# raspi-rnc.net
KiCad netlist of a schematic drawn in EAGLE
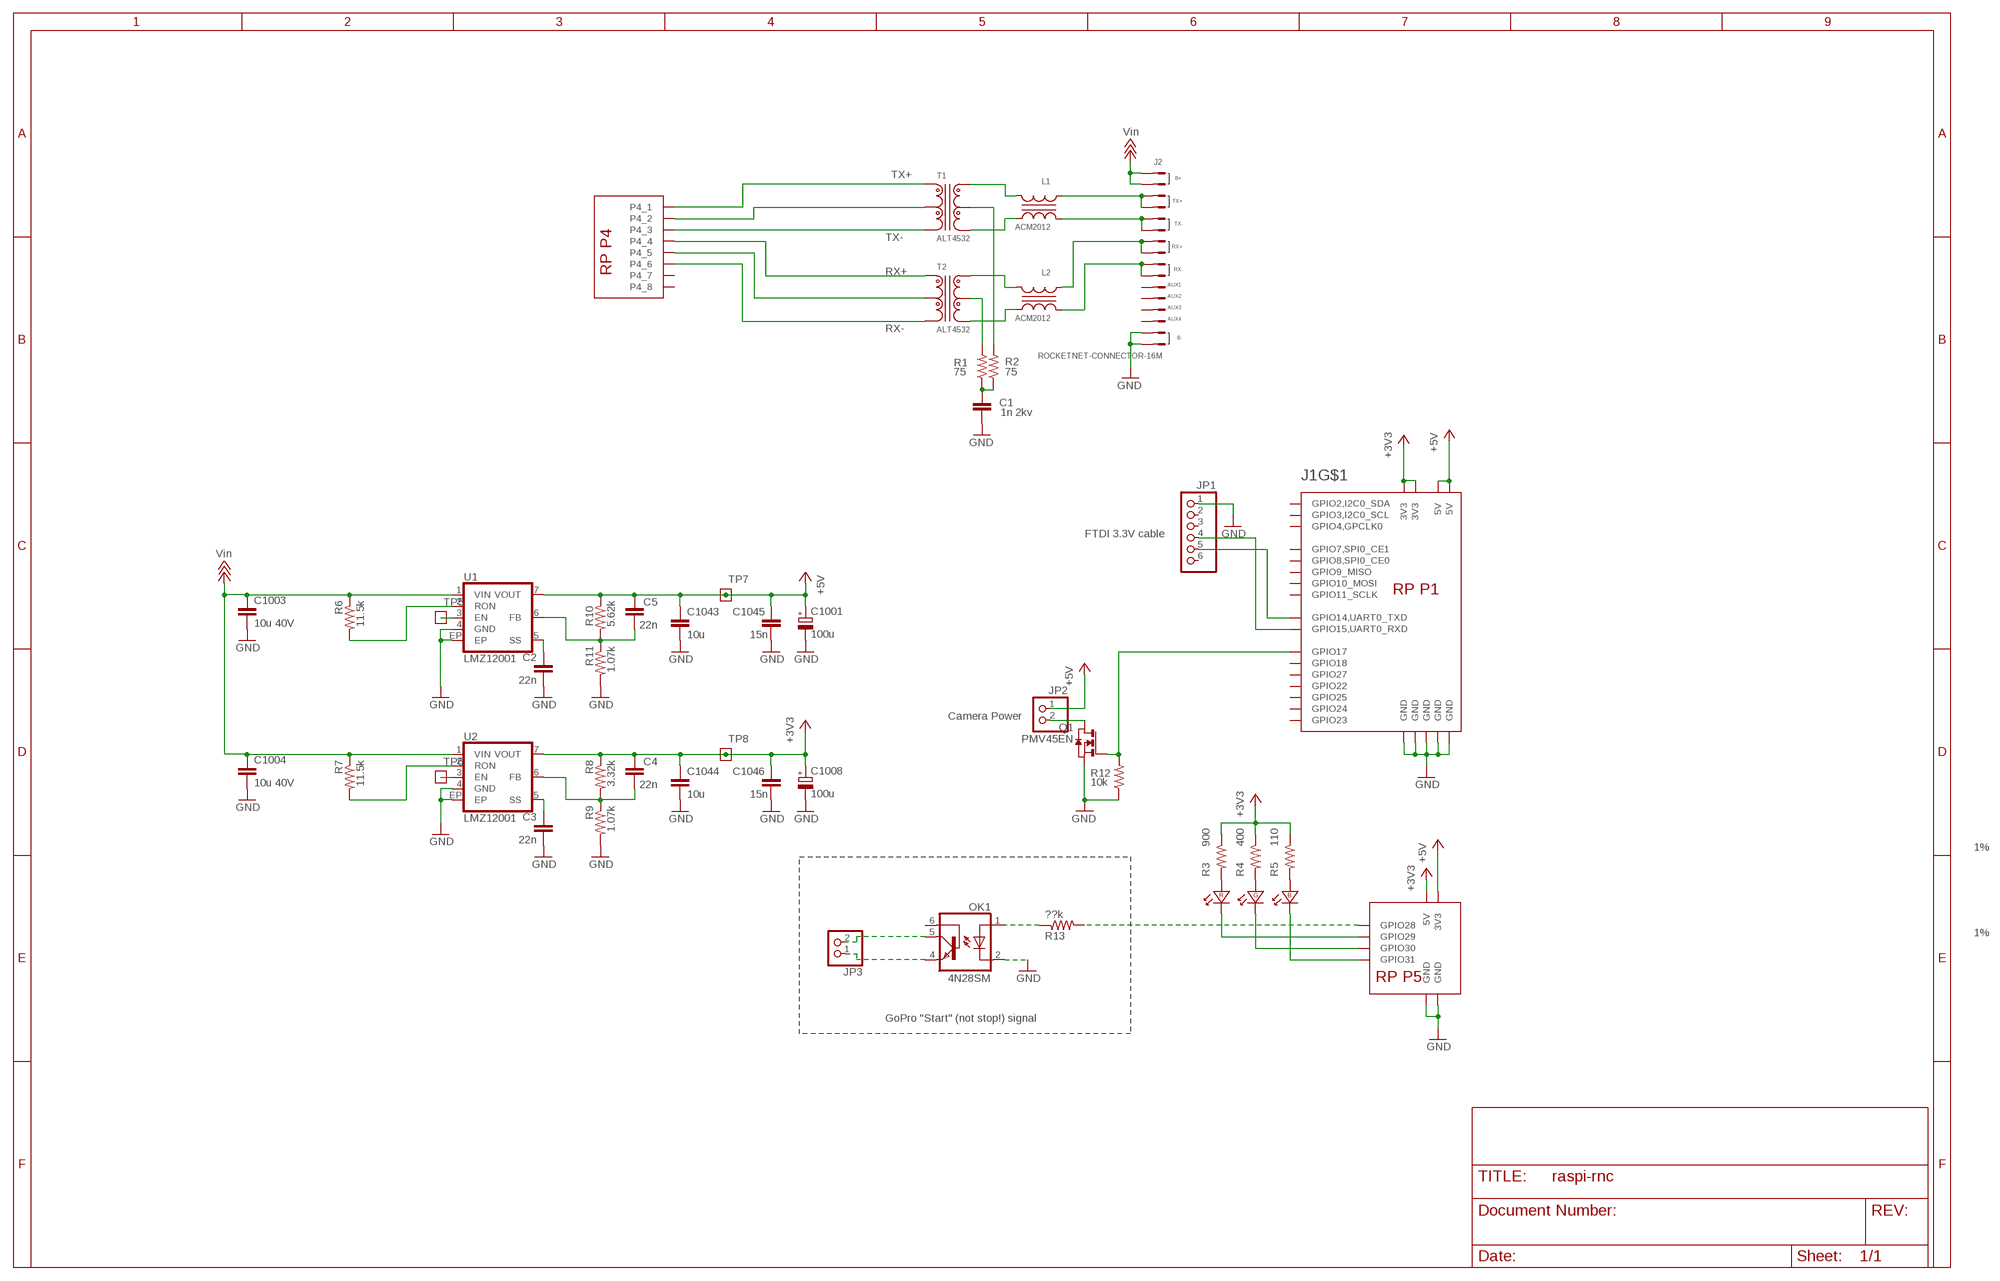
[diagram p0: schematic, sheet 1]

(export (version "E")
  (design (tool "Eeschema 10.0.6"))
  (components
    (comp (ref "C1")
      (value "1n 2kv")
      (footprint "eagle-import:0603-B-NOSILK")
      (libsource (lib "eagle-import") (part "C-EU0603-B-NOSILK"))
    )
    (comp (ref "C2")
      (value "22n")
      (footprint "eagle-import:0603-B-NOSILK")
      (libsource (lib "eagle-import") (part "C-EU0603-B-NOSILK"))
    )
    (comp (ref "C3")
      (value "22n")
      (footprint "eagle-import:0603-B-NOSILK")
      (libsource (lib "eagle-import") (part "C-EU0603-B-NOSILK"))
    )
    (comp (ref "C4")
      (value "22n")
      (footprint "eagle-import:0603-B-NOSILK")
      (libsource (lib "eagle-import") (part "C-EU0603-B-NOSILK"))
    )
    (comp (ref "C5")
      (value "22n")
      (footprint "eagle-import:0603-B-NOSILK")
      (libsource (lib "eagle-import") (part "C-EU0603-B-NOSILK"))
    )
    (comp (ref "C1001")
      (value "100u")
      (footprint "eagle-import:D_7343-31R")
      (libsource (lib "eagle-import") (part "CPOL-EUD/7343-31R"))
    )
    (comp (ref "C1003")
      (value "10u 40V")
      (footprint "eagle-import:0805-B-NOSILK")
      (libsource (lib "eagle-import") (part "C-EU0805-B-NOSILK"))
    )
    (comp (ref "C1004")
      (value "10u 40V")
      (footprint "eagle-import:0805-B-NOSILK")
      (libsource (lib "eagle-import") (part "C-EU0805-B-NOSILK"))
    )
    (comp (ref "C1008")
      (value "100u")
      (footprint "eagle-import:D_7343-31R")
      (libsource (lib "eagle-import") (part "CPOL-EUD/7343-31R"))
    )
    (comp (ref "C1043")
      (value "10u")
      (footprint "eagle-import:0805-B-NOSILK")
      (libsource (lib "eagle-import") (part "C-EU0805-B-NOSILK"))
    )
    (comp (ref "C1044")
      (value "10u")
      (footprint "eagle-import:0805-B-NOSILK")
      (libsource (lib "eagle-import") (part "C-EU0805-B-NOSILK"))
    )
    (comp (ref "C1045")
      (value "15n")
      (footprint "eagle-import:0603-B-NOSILK")
      (libsource (lib "eagle-import") (part "C-EU0603-B-NOSILK"))
    )
    (comp (ref "C1046")
      (value "15n")
      (footprint "eagle-import:0603-B-NOSILK")
      (libsource (lib "eagle-import") (part "C-EU0603-B-NOSILK"))
    )
    (comp (ref "J1")
      (value "RP-REV2-MOAR")
      (footprint "eagle-import:RP_REV2_MOAR")
      (libsource (lib "eagle-import") (part "RP-REV2-MOAR"))
    )
    (comp (ref "J2")
      (value "ROCKETNET-CONNECTOR-16M")
      (footprint "eagle-import:ROCKETNET-M-16")
      (libsource (lib "eagle-import") (part "ROCKETNET-CONNECTOR-16M"))
    )
    (comp (ref "JP1")
      (value "PINHD-1X6")
      (footprint "eagle-import:1X06")
      (libsource (lib "eagle-import") (part "PINHD-1X6"))
    )
    (comp (ref "JP2")
      (value "PINHD-1X2")
      (footprint "eagle-import:1X02")
      (libsource (lib "eagle-import") (part "PINHD-1X2"))
    )
    (comp (ref "JP3")
      (value "PINHD-1X2")
      (footprint "eagle-import:1X02")
      (libsource (lib "eagle-import") (part "PINHD-1X2"))
    )
    (comp (ref "L1")
      (value "ACM2012")
      (footprint "eagle-import:TDK-ACM2012")
      (libsource (lib "eagle-import") (part "ACM2012"))
    )
    (comp (ref "L2")
      (value "ACM2012")
      (footprint "eagle-import:TDK-ACM2012")
      (libsource (lib "eagle-import") (part "ACM2012"))
    )
    (comp (ref "LED3")
      (value "LED_RGB_PLCC-6")
      (footprint "eagle-import:PLCC-6")
      (libsource (lib "eagle-import") (part "LED_RGB_PLCC-6"))
    )
    (comp (ref "OK1")
      (value "4N28SM")
      (footprint "eagle-import:DIL6-SMD")
      (fields (field (name "MF") "FAIRCHILD SEMICONDUCTOR") (field (name "MPN") "4N28S-M"))
      (libsource (lib "eagle-import") (part "4N?MS28"))
    )
    (comp (ref "Q1")
      (value "PMV45EN")
      (footprint "eagle-import:SOT23")
      (libsource (lib "eagle-import") (part "PMV45EN"))
    )
    (comp (ref "R1")
      (value "75")
      (footprint "eagle-import:0603-B-NOSILK")
      (libsource (lib "eagle-import") (part "R-US_0603-B-NOSILK"))
    )
    (comp (ref "R2")
      (value "75")
      (footprint "eagle-import:0603-B-NOSILK")
      (libsource (lib "eagle-import") (part "R-US_0603-B-NOSILK"))
    )
    (comp (ref "R3")
      (value "900")
      (footprint "eagle-import:0603-B-NOSILK")
      (libsource (lib "eagle-import") (part "R-US_0603-B-NOSILK"))
    )
    (comp (ref "R4")
      (value "400")
      (footprint "eagle-import:0603-B-NOSILK")
      (libsource (lib "eagle-import") (part "R-US_0603-B-NOSILK"))
    )
    (comp (ref "R5")
      (value "110")
      (footprint "eagle-import:0603-B-NOSILK")
      (libsource (lib "eagle-import") (part "R-US_0603-B-NOSILK"))
    )
    (comp (ref "R6")
      (value "11.5k")
      (footprint "eagle-import:0603-B-NOSILK")
      (libsource (lib "eagle-import") (part "R-US_0603-B-NOSILK"))
    )
    (comp (ref "R7")
      (value "11.5k")
      (footprint "eagle-import:0603-B-NOSILK")
      (libsource (lib "eagle-import") (part "R-US_0603-B-NOSILK"))
    )
    (comp (ref "R8")
      (value "3.32k")
      (footprint "eagle-import:0603-B-NOSILK")
      (libsource (lib "eagle-import") (part "R-US_0603-B-NOSILK"))
    )
    (comp (ref "R9")
      (value "1.07k")
      (footprint "eagle-import:0603-B-NOSILK")
      (libsource (lib "eagle-import") (part "R-US_0603-B-NOSILK"))
    )
    (comp (ref "R10")
      (value "5.62k")
      (footprint "eagle-import:0603-B-NOSILK")
      (libsource (lib "eagle-import") (part "R-US_0603-B-NOSILK"))
    )
    (comp (ref "R11")
      (value "1.07k")
      (footprint "eagle-import:0603-B-NOSILK")
      (libsource (lib "eagle-import") (part "R-US_0603-B-NOSILK"))
    )
    (comp (ref "R12")
      (value "10k")
      (footprint "eagle-import:0603-B-NOSILK")
      (libsource (lib "eagle-import") (part "R-US_0603-B-NOSILK"))
    )
    (comp (ref "R13")
      (value "??k")
      (footprint "eagle-import:0603-B-NOSILK")
      (libsource (lib "eagle-import") (part "R-US_0603-B-NOSILK"))
    )
    (comp (ref "T1")
      (value "ALT4532")
      (footprint "eagle-import:TDK-ALT4532")
      (libsource (lib "eagle-import") (part "ALT4532"))
    )
    (comp (ref "T2")
      (value "ALT4532")
      (footprint "eagle-import:TDK-ALT4532")
      (libsource (lib "eagle-import") (part "ALT4532"))
    )
    (comp (ref "TP5")
      (value "TEST-POINT")
      (footprint "eagle-import:2MM-TEST-POINT")
      (libsource (lib "eagle-import") (part "TEST-POINT"))
    )
    (comp (ref "TP6")
      (value "TEST-POINT")
      (footprint "eagle-import:2MM-TEST-POINT")
      (libsource (lib "eagle-import") (part "TEST-POINT"))
    )
    (comp (ref "TP7")
      (value "TEST-POINT")
      (footprint "eagle-import:2MM-TEST-POINT")
      (libsource (lib "eagle-import") (part "TEST-POINT"))
    )
    (comp (ref "TP8")
      (value "TEST-POINT")
      (footprint "eagle-import:2MM-TEST-POINT")
      (libsource (lib "eagle-import") (part "TEST-POINT"))
    )
    (comp (ref "U1")
      (value "LMZ12001")
      (footprint "eagle-import:TO-PMOD-7")
      (libsource (lib "eagle-import") (part "LMZ14203"))
    )
    (comp (ref "U2")
      (value "LMZ12001")
      (footprint "eagle-import:TO-PMOD-7")
      (libsource (lib "eagle-import") (part "LMZ14203"))
    )
  )
  (nets
    (net (code "1") (name "+3V3") (class "Default")
      (node (ref "C1008") (pin "+") (pinfunction "+_+") (pintype "passive"))
      (node (ref "C1044") (pin "1") (pinfunction "1_1") (pintype "passive"))
      (node (ref "C1046") (pin "1") (pinfunction "1_1") (pintype "passive"))
      (node (ref "C4") (pin "1") (pinfunction "1_1") (pintype "passive"))
      (node (ref "J1") (pin "P1_1") (pinfunction "3V3_P1_1") (pintype "power_in"))
      (node (ref "J1") (pin "P1_17") (pinfunction "3V3_P1_17") (pintype "power_in"))
      (node (ref "J1") (pin "P5_1") (pinfunction "5V_P5_1") (pintype "power_in"))
      (node (ref "R3") (pin "1") (pinfunction "1_1") (pintype "passive"))
      (node (ref "R4") (pin "1") (pinfunction "1_1") (pintype "passive"))
      (node (ref "R5") (pin "1") (pinfunction "1_1") (pintype "passive"))
      (node (ref "R8") (pin "1") (pinfunction "1_1") (pintype "passive"))
      (node (ref "TP8") (pin "1") (pinfunction "1_1") (pintype "passive"))
      (node (ref "U2") (pin "7") (pinfunction "VOUT_7") (pintype "bidirectional"))
    )
    (net (code "2") (name "+5V") (class "Default")
      (node (ref "C1001") (pin "+") (pinfunction "+_+") (pintype "passive"))
      (node (ref "C1043") (pin "1") (pinfunction "1_1") (pintype "passive"))
      (node (ref "C1045") (pin "1") (pinfunction "1_1") (pintype "passive"))
      (node (ref "C5") (pin "1") (pinfunction "1_1") (pintype "passive"))
      (node (ref "J1") (pin "P1_2") (pinfunction "5V_P1_2") (pintype "power_in"))
      (node (ref "J1") (pin "P1_4") (pinfunction "5V_P1_4") (pintype "power_in"))
      (node (ref "J1") (pin "P5_2") (pinfunction "3V3_P5_2") (pintype "power_in"))
      (node (ref "JP2") (pin "1") (pinfunction "1_1") (pintype "passive"))
      (node (ref "R10") (pin "1") (pinfunction "1_1") (pintype "passive"))
      (node (ref "TP7") (pin "1") (pinfunction "1_1") (pintype "passive"))
      (node (ref "U1") (pin "7") (pinfunction "VOUT_7") (pintype "bidirectional"))
    )
    (net (code "3") (name "GND") (class "Default")
      (node (ref "C1") (pin "2") (pinfunction "2_2") (pintype "passive"))
      (node (ref "C1001") (pin "-") (pinfunction "-_-") (pintype "passive"))
      (node (ref "C1003") (pin "2") (pinfunction "2_2") (pintype "passive"))
      (node (ref "C1004") (pin "2") (pinfunction "2_2") (pintype "passive"))
      (node (ref "C1008") (pin "-") (pinfunction "-_-") (pintype "passive"))
      (node (ref "C1043") (pin "2") (pinfunction "2_2") (pintype "passive"))
      (node (ref "C1044") (pin "2") (pinfunction "2_2") (pintype "passive"))
      (node (ref "C1045") (pin "2") (pinfunction "2_2") (pintype "passive"))
      (node (ref "C1046") (pin "2") (pinfunction "2_2") (pintype "passive"))
      (node (ref "C2") (pin "2") (pinfunction "2_2") (pintype "passive"))
      (node (ref "C3") (pin "2") (pinfunction "2_2") (pintype "passive"))
      (node (ref "J1") (pin "P1_14") (pinfunction "GND_P1_14") (pintype "power_in"))
      (node (ref "J1") (pin "P1_20") (pinfunction "GND_P1_20") (pintype "power_in"))
      (node (ref "J1") (pin "P1_25") (pinfunction "GND_P1_25") (pintype "power_in"))
      (node (ref "J1") (pin "P1_6") (pinfunction "GND_P1_6") (pintype "power_in"))
      (node (ref "J1") (pin "P1_9") (pinfunction "GND_P1_9") (pintype "power_in"))
      (node (ref "J1") (pin "P5_7") (pinfunction "GND_P5_7") (pintype "power_in"))
      (node (ref "J1") (pin "P5_8") (pinfunction "GND_P5_8") (pintype "power_in"))
      (node (ref "J2") (pin "B-@1") (pinfunction "B-_B-@1") (pintype "power_in"))
      (node (ref "J2") (pin "B-@2") (pinfunction "B-_B-@2") (pintype "power_in"))
      (node (ref "JP1") (pin "1") (pinfunction "1_1") (pintype "passive"))
      (node (ref "OK1") (pin "2") (pinfunction "C_2") (pintype "passive"))
      (node (ref "Q1") (pin "2") (pinfunction "S_2") (pintype "passive"))
      (node (ref "R11") (pin "2") (pinfunction "2_2") (pintype "passive"))
      (node (ref "R12") (pin "1") (pinfunction "1_1") (pintype "passive"))
      (node (ref "R9") (pin "2") (pinfunction "2_2") (pintype "passive"))
      (node (ref "U1") (pin "4") (pinfunction "GND_4") (pintype "bidirectional"))
      (node (ref "U1") (pin "EP") (pinfunction "EP_EP") (pintype "bidirectional"))
      (node (ref "U2") (pin "4") (pinfunction "GND_4") (pintype "bidirectional"))
      (node (ref "U2") (pin "EP") (pinfunction "EP_EP") (pintype "bidirectional"))
    )
    (net (code "4") (name "Net-(C1-Pad1)") (class "Default")
      (node (ref "C1") (pin "1") (pinfunction "1_1") (pintype "passive"))
      (node (ref "R1") (pin "1") (pinfunction "1_1") (pintype "passive"))
      (node (ref "R2") (pin "1") (pinfunction "1_1") (pintype "passive"))
    )
    (net (code "5") (name "Net-(J1-PadP4_1)") (class "Default")
      (node (ref "J1") (pin "P4_1") (pinfunction "P4_1_P4_1") (pintype "passive"))
      (node (ref "T1") (pin "1") (pinfunction "1_1") (pintype "passive"))
    )
    (net (code "6") (name "Net-(J1-PadP4_2)") (class "Default")
      (node (ref "J1") (pin "P4_2") (pinfunction "P4_2_P4_2") (pintype "passive"))
      (node (ref "T1") (pin "6") (pinfunction "6_6") (pintype "passive"))
    )
    (net (code "7") (name "Net-(J1-PadP4_3)") (class "Default")
      (node (ref "J1") (pin "P4_3") (pinfunction "P4_3_P4_3") (pintype "passive"))
      (node (ref "T1") (pin "2") (pinfunction "2_2") (pintype "passive"))
    )
    (net (code "8") (name "Net-(J1-PadP4_4)") (class "Default")
      (node (ref "J1") (pin "P4_4") (pinfunction "P4_4_P4_4") (pintype "passive"))
      (node (ref "T2") (pin "1") (pinfunction "1_1") (pintype "passive"))
    )
    (net (code "9") (name "Net-(J1-PadP4_5)") (class "Default")
      (node (ref "J1") (pin "P4_5") (pinfunction "P4_5_P4_5") (pintype "passive"))
      (node (ref "T2") (pin "6") (pinfunction "6_6") (pintype "passive"))
    )
    (net (code "10") (name "Net-(J1-PadP4_6)") (class "Default")
      (node (ref "J1") (pin "P4_6") (pinfunction "P4_6_P4_6") (pintype "passive"))
      (node (ref "T2") (pin "2") (pinfunction "2_2") (pintype "passive"))
    )
    (net (code "11") (name "Net-(J1A-GPIO14,UART0_TXD)") (class "Default")
      (node (ref "J1") (pin "P1_8") (pinfunction "GPIO14,UART0_TXD_P1_8") (pintype "bidirectional"))
      (node (ref "JP1") (pin "5") (pinfunction "5_5") (pintype "passive"))
    )
    (net (code "12") (name "Net-(J1A-GPIO15,UART0_RXD)") (class "Default")
      (node (ref "J1") (pin "P1_10") (pinfunction "GPIO15,UART0_RXD_P1_10") (pintype "bidirectional"))
      (node (ref "JP1") (pin "4") (pinfunction "4_4") (pintype "passive"))
    )
    (net (code "13") (name "Net-(J1A-GPIO17)") (class "Default")
      (node (ref "J1") (pin "P1_26") (pinfunction "GPIO17_P1_26") (pintype "bidirectional"))
      (node (ref "Q1") (pin "1") (pinfunction "G_1") (pintype "passive"))
      (node (ref "R12") (pin "2") (pinfunction "2_2") (pintype "passive"))
    )
    (net (code "14") (name "Net-(J1C-GPIO28)") (class "Default")
      (node (ref "J1") (pin "P5_3") (pinfunction "GPIO28_P5_3") (pintype "bidirectional"))
      (node (ref "R13") (pin "2") (pinfunction "2_2") (pintype "passive"))
    )
    (net (code "15") (name "Net-(J1C-GPIO29)") (class "Default")
      (node (ref "J1") (pin "P5_4") (pinfunction "GPIO29_P5_4") (pintype "bidirectional"))
      (node (ref "LED3") (pin "6") (pinfunction "K_6") (pintype "passive"))
    )
    (net (code "16") (name "Net-(J1C-GPIO30)") (class "Default")
      (node (ref "J1") (pin "P5_5") (pinfunction "GPIO30_P5_5") (pintype "bidirectional"))
      (node (ref "LED3") (pin "2") (pinfunction "K_2") (pintype "passive"))
    )
    (net (code "17") (name "Net-(J1C-GPIO31)") (class "Default")
      (node (ref "J1") (pin "P5_6") (pinfunction "GPIO31_P5_6") (pintype "bidirectional"))
      (node (ref "LED3") (pin "5") (pinfunction "K_5") (pintype "passive"))
    )
    (net (code "18") (name "Net-(J2-RX+-PadR+@5)") (class "Default")
      (node (ref "J2") (pin "R+@5") (pinfunction "RX+_R+@5") (pintype "passive"))
      (node (ref "J2") (pin "R+@7") (pinfunction "RX+_R+@7") (pintype "passive"))
      (node (ref "L2") (pin "1") (pinfunction "1_1") (pintype "passive"))
    )
    (net (code "19") (name "Net-(J2-RX--PadR-@3)") (class "Default")
      (node (ref "J2") (pin "R-@3") (pinfunction "RX-_R-@3") (pintype "passive"))
      (node (ref "J2") (pin "R-@4") (pinfunction "RX-_R-@4") (pintype "passive"))
      (node (ref "L2") (pin "2") (pinfunction "2_2") (pintype "passive"))
    )
    (net (code "20") (name "Net-(J2-TX+-PadT+@13)") (class "Default")
      (node (ref "J2") (pin "T+@13") (pinfunction "TX+_T+@13") (pintype "passive"))
      (node (ref "J2") (pin "T+@14") (pinfunction "TX+_T+@14") (pintype "passive"))
      (node (ref "L1") (pin "1") (pinfunction "1_1") (pintype "passive"))
    )
    (net (code "21") (name "Net-(J2-TX--PadT-@11)") (class "Default")
      (node (ref "J2") (pin "T-@11") (pinfunction "TX-_T-@11") (pintype "passive"))
      (node (ref "J2") (pin "T-@9") (pinfunction "TX-_T-@9") (pintype "passive"))
      (node (ref "L1") (pin "2") (pinfunction "2_2") (pintype "passive"))
    )
    (net (code "22") (name "Net-(L1-Pad3)") (class "Default")
      (node (ref "L1") (pin "3") (pinfunction "3_3") (pintype "passive"))
      (node (ref "T1") (pin "4") (pinfunction "4_4") (pintype "passive"))
    )
    (net (code "23") (name "Net-(L1-Pad4)") (class "Default")
      (node (ref "L1") (pin "4") (pinfunction "4_4") (pintype "passive"))
      (node (ref "T1") (pin "5") (pinfunction "5_5") (pintype "passive"))
    )
    (net (code "24") (name "Net-(L2-Pad3)") (class "Default")
      (node (ref "L2") (pin "3") (pinfunction "3_3") (pintype "passive"))
      (node (ref "T2") (pin "4") (pinfunction "4_4") (pintype "passive"))
    )
    (net (code "25") (name "Net-(L2-Pad4)") (class "Default")
      (node (ref "L2") (pin "4") (pinfunction "4_4") (pintype "passive"))
      (node (ref "T2") (pin "5") (pinfunction "5_5") (pintype "passive"))
    )
    (net (code "26") (name "Net-(LED3A-A)") (class "Default")
      (node (ref "LED3") (pin "4") (pinfunction "A_4") (pintype "passive"))
      (node (ref "R5") (pin "2") (pinfunction "2_2") (pintype "passive"))
    )
    (net (code "27") (name "Net-(LED3B-A)") (class "Default")
      (node (ref "LED3") (pin "3") (pinfunction "A_3") (pintype "passive"))
      (node (ref "R4") (pin "2") (pinfunction "2_2") (pintype "passive"))
    )
    (net (code "28") (name "Net-(LED3D-A)") (class "Default")
      (node (ref "LED3") (pin "1") (pinfunction "A_1") (pintype "passive"))
      (node (ref "R3") (pin "2") (pinfunction "2_2") (pintype "passive"))
    )
    (net (code "29") (name "Net-(OK1-A)") (class "Default")
      (node (ref "OK1") (pin "1") (pinfunction "A_1") (pintype "passive"))
      (node (ref "R13") (pin "1") (pinfunction "1_1") (pintype "passive"))
    )
    (net (code "30") (name "Net-(OK1-COL)") (class "Default")
      (node (ref "JP3") (pin "2") (pinfunction "2_2") (pintype "passive"))
      (node (ref "OK1") (pin "5") (pinfunction "COL_5") (pintype "passive"))
    )
    (net (code "31") (name "Net-(OK1-EMI)") (class "Default")
      (node (ref "JP3") (pin "1") (pinfunction "1_1") (pintype "passive"))
      (node (ref "OK1") (pin "4") (pinfunction "EMI_4") (pintype "passive"))
    )
    (net (code "32") (name "Net-(Q1-D)") (class "Default")
      (node (ref "JP2") (pin "2") (pinfunction "2_2") (pintype "passive"))
      (node (ref "Q1") (pin "3") (pinfunction "D_3") (pintype "passive"))
    )
    (net (code "33") (name "Net-(R1-Pad2)") (class "Default")
      (node (ref "R1") (pin "2") (pinfunction "2_2") (pintype "passive"))
      (node (ref "T2") (pin "3") (pinfunction "3_3") (pintype "passive"))
    )
    (net (code "34") (name "Net-(R2-Pad2)") (class "Default")
      (node (ref "R2") (pin "2") (pinfunction "2_2") (pintype "passive"))
      (node (ref "T1") (pin "3") (pinfunction "3_3") (pintype "passive"))
    )
    (net (code "35") (name "Net-(U1-EN)") (class "Default")
      (node (ref "TP5") (pin "1") (pinfunction "1_1") (pintype "passive"))
      (node (ref "U1") (pin "3") (pinfunction "EN_3") (pintype "bidirectional"))
    )
    (net (code "36") (name "Net-(U1-FB)") (class "Default")
      (node (ref "C5") (pin "2") (pinfunction "2_2") (pintype "passive"))
      (node (ref "R10") (pin "2") (pinfunction "2_2") (pintype "passive"))
      (node (ref "R11") (pin "1") (pinfunction "1_1") (pintype "passive"))
      (node (ref "U1") (pin "6") (pinfunction "FB_6") (pintype "bidirectional"))
    )
    (net (code "37") (name "Net-(U1-RON)") (class "Default")
      (node (ref "R6") (pin "2") (pinfunction "2_2") (pintype "passive"))
      (node (ref "U1") (pin "2") (pinfunction "RON_2") (pintype "bidirectional"))
    )
    (net (code "38") (name "Net-(U1-SS)") (class "Default")
      (node (ref "C2") (pin "1") (pinfunction "1_1") (pintype "passive"))
      (node (ref "U1") (pin "5") (pinfunction "SS_5") (pintype "bidirectional"))
    )
    (net (code "39") (name "Net-(U2-EN)") (class "Default")
      (node (ref "TP6") (pin "1") (pinfunction "1_1") (pintype "passive"))
      (node (ref "U2") (pin "3") (pinfunction "EN_3") (pintype "bidirectional"))
    )
    (net (code "40") (name "Net-(U2-FB)") (class "Default")
      (node (ref "C4") (pin "2") (pinfunction "2_2") (pintype "passive"))
      (node (ref "R8") (pin "2") (pinfunction "2_2") (pintype "passive"))
      (node (ref "R9") (pin "1") (pinfunction "1_1") (pintype "passive"))
      (node (ref "U2") (pin "6") (pinfunction "FB_6") (pintype "bidirectional"))
    )
    (net (code "41") (name "Net-(U2-RON)") (class "Default")
      (node (ref "R7") (pin "2") (pinfunction "2_2") (pintype "passive"))
      (node (ref "U2") (pin "2") (pinfunction "RON_2") (pintype "bidirectional"))
    )
    (net (code "42") (name "Net-(U2-SS)") (class "Default")
      (node (ref "C3") (pin "1") (pinfunction "1_1") (pintype "passive"))
      (node (ref "U2") (pin "5") (pinfunction "SS_5") (pintype "bidirectional"))
    )
    (net (code "43") (name "Vin") (class "Default")
      (node (ref "C1003") (pin "1") (pinfunction "1_1") (pintype "passive"))
      (node (ref "C1004") (pin "1") (pinfunction "1_1") (pintype "passive"))
      (node (ref "J2") (pin "B+@15") (pinfunction "B+_B+@15") (pintype "power_in"))
      (node (ref "J2") (pin "B+@16") (pinfunction "B+_B+@16") (pintype "power_in"))
      (node (ref "R6") (pin "1") (pinfunction "1_1") (pintype "passive"))
      (node (ref "R7") (pin "1") (pinfunction "1_1") (pintype "passive"))
      (node (ref "U1") (pin "1") (pinfunction "VIN_1") (pintype "bidirectional"))
      (node (ref "U2") (pin "1") (pinfunction "VIN_1") (pintype "bidirectional"))
    )
    (net (code "44") (name "unconnected-(J1-PadP4_7)") (class "Default")
      (node (ref "J1") (pin "P4_7") (pinfunction "P4_7_P4_7") (pintype "passive"))
    )
    (net (code "45") (name "unconnected-(J1-PadP4_8)") (class "Default")
      (node (ref "J1") (pin "P4_8") (pinfunction "P4_8_P4_8") (pintype "passive"))
    )
    (net (code "46") (name "unconnected-(J1A-GPIO2,I2C0_SDA-PadP1_3)") (class "Default")
      (node (ref "J1") (pin "P1_3") (pinfunction "GPIO2,I2C0_SDA_P1_3") (pintype "bidirectional"))
    )
    (net (code "47") (name "unconnected-(J1A-GPIO3,I2C0_SCL-PadP1_5)") (class "Default")
      (node (ref "J1") (pin "P1_5") (pinfunction "GPIO3,I2C0_SCL_P1_5") (pintype "bidirectional"))
    )
    (net (code "48") (name "unconnected-(J1A-GPIO4,GPCLK0-PadP1_7)") (class "Default")
      (node (ref "J1") (pin "P1_7") (pinfunction "GPIO4,GPCLK0_P1_7") (pintype "bidirectional"))
    )
    (net (code "49") (name "unconnected-(J1A-GPIO7,SPI0_CE1-PadP1_11)") (class "Default")
      (node (ref "J1") (pin "P1_11") (pinfunction "GPIO7,SPI0_CE1_P1_11") (pintype "bidirectional"))
    )
    (net (code "50") (name "unconnected-(J1A-GPIO8,SPI0_CE0-PadP1_12)") (class "Default")
      (node (ref "J1") (pin "P1_12") (pinfunction "GPIO8,SPI0_CE0_P1_12") (pintype "bidirectional"))
    )
    (net (code "51") (name "unconnected-(J1A-GPIO9_MISO-PadP1_21)") (class "Default")
      (node (ref "J1") (pin "P1_21") (pinfunction "GPIO9_MISO_P1_21") (pintype "bidirectional"))
    )
    (net (code "52") (name "unconnected-(J1A-GPIO10_MOSI-PadP1_19)") (class "Default")
      (node (ref "J1") (pin "P1_19") (pinfunction "GPIO10_MOSI_P1_19") (pintype "bidirectional"))
    )
    (net (code "53") (name "unconnected-(J1A-GPIO11_SCLK-PadP1_23)") (class "Default")
      (node (ref "J1") (pin "P1_23") (pinfunction "GPIO11_SCLK_P1_23") (pintype "bidirectional"))
    )
    (net (code "54") (name "unconnected-(J1A-GPIO18-PadP1_24)") (class "Default")
      (node (ref "J1") (pin "P1_24") (pinfunction "GPIO18_P1_24") (pintype "bidirectional"))
    )
    (net (code "55") (name "unconnected-(J1A-GPIO22-PadP1_15)") (class "Default")
      (node (ref "J1") (pin "P1_15") (pinfunction "GPIO22_P1_15") (pintype "bidirectional"))
    )
    (net (code "56") (name "unconnected-(J1A-GPIO23-PadP1_16)") (class "Default")
      (node (ref "J1") (pin "P1_16") (pinfunction "GPIO23_P1_16") (pintype "bidirectional"))
    )
    (net (code "57") (name "unconnected-(J1A-GPIO24-PadP1_18)") (class "Default")
      (node (ref "J1") (pin "P1_18") (pinfunction "GPIO24_P1_18") (pintype "bidirectional"))
    )
    (net (code "58") (name "unconnected-(J1A-GPIO25-PadP1_22)") (class "Default")
      (node (ref "J1") (pin "P1_22") (pinfunction "GPIO25_P1_22") (pintype "bidirectional"))
    )
    (net (code "59") (name "unconnected-(J1A-GPIO27-PadP1_13)") (class "Default")
      (node (ref "J1") (pin "P1_13") (pinfunction "GPIO27_P1_13") (pintype "bidirectional"))
    )
    (net (code "60") (name "unconnected-(J2-AUX1-PadA1)") (class "Default")
      (node (ref "J2") (pin "A1") (pinfunction "AUX1_A1") (pintype "passive"))
    )
    (net (code "61") (name "unconnected-(J2-AUX2-PadA2)") (class "Default")
      (node (ref "J2") (pin "A2") (pinfunction "AUX2_A2") (pintype "passive"))
    )
    (net (code "62") (name "unconnected-(J2-AUX3-PadA3)") (class "Default")
      (node (ref "J2") (pin "A3") (pinfunction "AUX3_A3") (pintype "passive"))
    )
    (net (code "63") (name "unconnected-(J2-AUX4-PadA4)") (class "Default")
      (node (ref "J2") (pin "A4") (pinfunction "AUX4_A4") (pintype "passive"))
    )
    (net (code "64") (name "unconnected-(JP1-Pad2)") (class "Default")
      (node (ref "JP1") (pin "2") (pinfunction "2_2") (pintype "passive"))
    )
    (net (code "65") (name "unconnected-(JP1-Pad3)") (class "Default")
      (node (ref "JP1") (pin "3") (pinfunction "3_3") (pintype "passive"))
    )
    (net (code "66") (name "unconnected-(JP1-Pad6)") (class "Default")
      (node (ref "JP1") (pin "6") (pinfunction "6_6") (pintype "passive"))
    )
    (net (code "67") (name "unconnected-(OK1-BAS-Pad6)") (class "Default")
      (node (ref "OK1") (pin "6") (pinfunction "BAS_6") (pintype "passive"))
    )
  )
)
